# opcouplers.net
KiCad netlist of a schematic drawn in Altium Designer
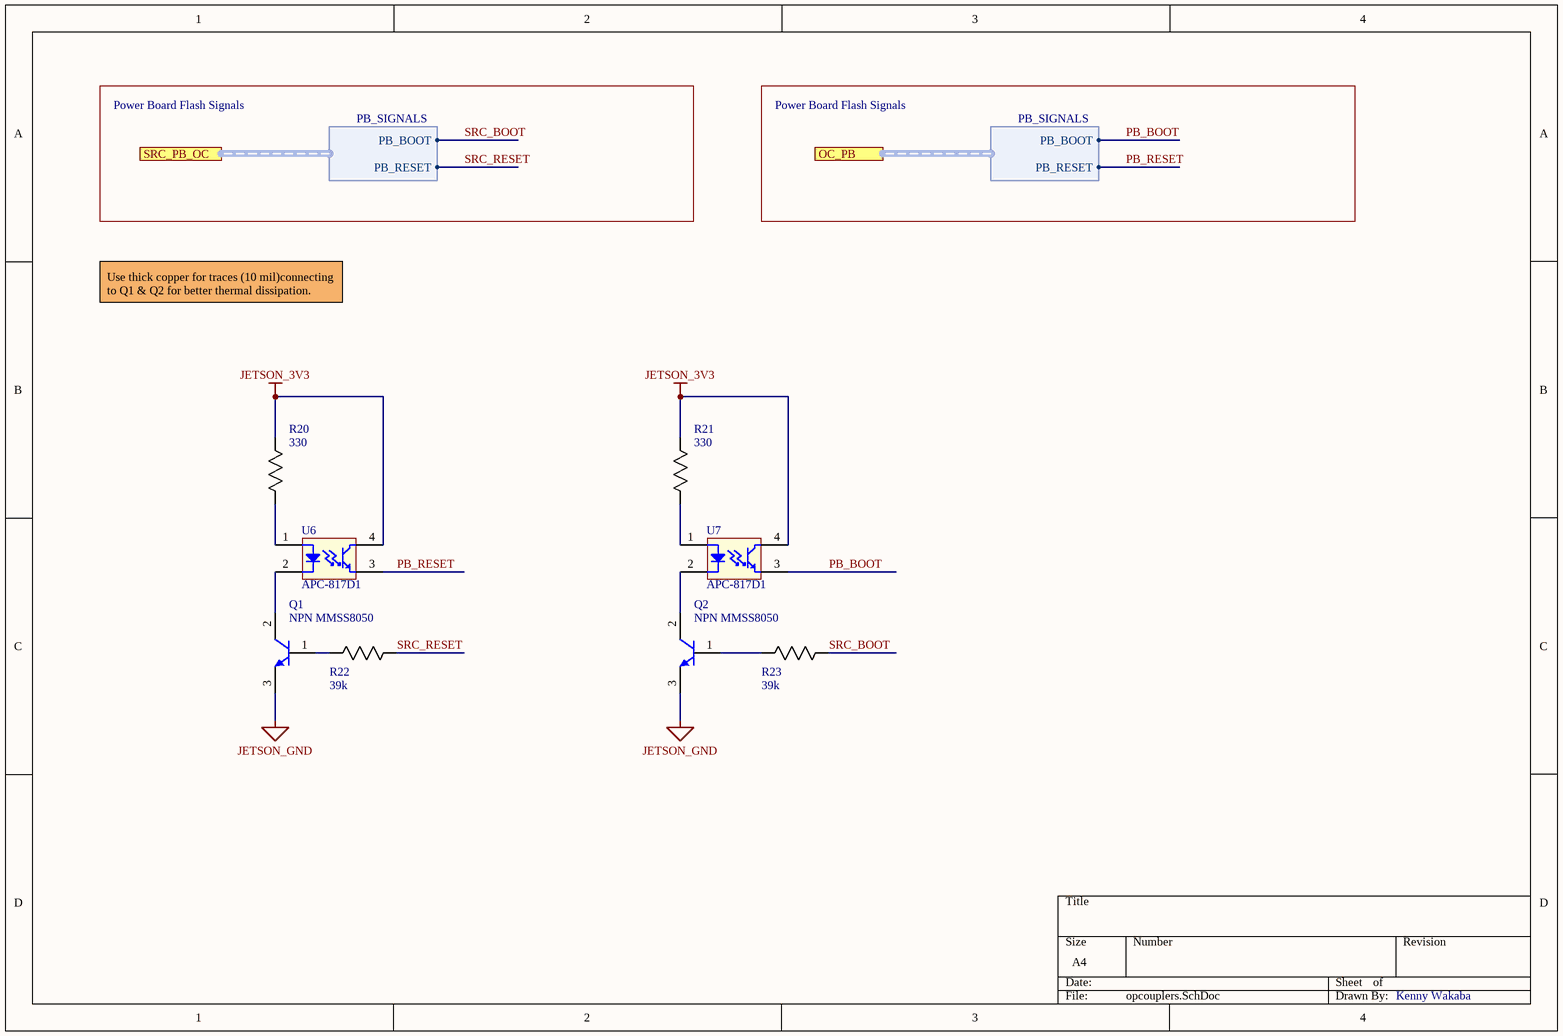
[diagram p0: opcouplers.SchDoc]

(export (version "E")
  (design (tool "Eeschema 10.0.6"))
  (components
    (comp (ref "Q1")
      (value "NPN MMSS8050")
      (footprint "SOT95P237X112-3N")
      (description "Bipolar (BJT) Transistor NPN 25 V 1.5 A 100MHz 625 mW Surface Mount SOT-23")
      (fields (field (name "PART NUMBER") "N_BJT MMSS8050"))
      (libsource (lib "Transistor_Library") (part "NPN MMSS8050"))
    )
    (comp (ref "Q2")
      (value "NPN MMSS8050")
      (footprint "SOT95P237X112-3N")
      (description "Bipolar (BJT) Transistor NPN 25 V 1.5 A 100MHz 625 mW Surface Mount SOT-23")
      (fields (field (name "PART NUMBER") "N_BJT MMSS8050"))
      (libsource (lib "Transistor_Library") (part "NPN MMSS8050"))
    )
    (comp (ref "R20")
      (value "330")
      (footprint "0603")
      (description "Default Resistor Symbol")
      (fields (field (name "TOLERANCE") "5%") (field (name "PART NUMBER") "RES 330.0 1/8W - 5%"))
      (libsource (lib "Resistor_Library") (part "RES_DEFAULT"))
    )
    (comp (ref "R21")
      (value "330")
      (footprint "0603")
      (description "Default Resistor Symbol")
      (fields (field (name "TOLERANCE") "5%") (field (name "PART NUMBER") "RES 330.0 1/8W - 5%"))
      (libsource (lib "Resistor_Library") (part "RES_DEFAULT"))
    )
    (comp (ref "R22")
      (value "39k")
      (footprint "0603")
      (description "Default Resistor Symbol")
      (fields (field (name "TOLERANCE") "1%") (field (name "PART NUMBER") "RES 39k 1/8W"))
      (libsource (lib "Resistor_Library") (part "RES_DEFAULT"))
    )
    (comp (ref "R23")
      (value "39k")
      (footprint "0603")
      (description "Default Resistor Symbol")
      (fields (field (name "TOLERANCE") "1%") (field (name "PART NUMBER") "RES 39k 1/8W"))
      (libsource (lib "Resistor_Library") (part "RES_DEFAULT"))
    )
    (comp (ref "U6")
      (value "APC-817D1")
      (footprint "APC-817D1")
      (description "DIP4, DC Input, Optocoupler")
      (libsource (lib "IC_Library") (part "APC-817D1"))
    )
    (comp (ref "U7")
      (value "APC-817D1")
      (footprint "APC-817D1")
      (description "DIP4, DC Input, Optocoupler")
      (libsource (lib "IC_Library") (part "APC-817D1"))
    )
  )
  (nets
    (net (code "2") (name "/PB_BOOT") (class "Default")
      (node (ref "U7") (pin "3") (pinfunction "3_3") (pintype "passive"))
    )
    (net (code "3") (name "/PB_RESET") (class "Default")
      (node (ref "U6") (pin "3") (pinfunction "3_3") (pintype "passive"))
    )
    (net (code "4") (name "/SRC_BOOT") (class "Default")
      (node (ref "R23") (pin "1") (pinfunction "R1_1") (pintype "passive"))
    )
    (net (code "5") (name "/SRC_RESET") (class "Default")
      (node (ref "R22") (pin "1") (pinfunction "R1_1") (pintype "passive"))
    )
    (net (code "7") (name "JETSON_3V3") (class "Default")
      (node (ref "R20") (pin "2") (pinfunction "R2_2") (pintype "passive"))
      (node (ref "R21") (pin "2") (pinfunction "R2_2") (pintype "passive"))
      (node (ref "U6") (pin "4") (pinfunction "4_4") (pintype "passive"))
      (node (ref "U7") (pin "4") (pinfunction "4_4") (pintype "passive"))
    )
    (net (code "8") (name "JETSON_GND") (class "Default")
      (node (ref "Q1") (pin "3") (pinfunction "E_3") (pintype "passive"))
      (node (ref "Q2") (pin "3") (pinfunction "E_3") (pintype "passive"))
    )
    (net (code "9") (name "Net-(Q1-B)") (class "Default")
      (node (ref "Q1") (pin "1") (pinfunction "B_1") (pintype "passive"))
      (node (ref "R22") (pin "2") (pinfunction "R2_2") (pintype "passive"))
    )
    (net (code "10") (name "Net-(Q1-C)") (class "Default")
      (node (ref "Q1") (pin "2") (pinfunction "C_2") (pintype "passive"))
      (node (ref "U6") (pin "2") (pinfunction "2_2") (pintype "passive"))
    )
    (net (code "11") (name "Net-(Q2-B)") (class "Default")
      (node (ref "Q2") (pin "1") (pinfunction "B_1") (pintype "passive"))
      (node (ref "R23") (pin "2") (pinfunction "R2_2") (pintype "passive"))
    )
    (net (code "12") (name "Net-(Q2-C)") (class "Default")
      (node (ref "Q2") (pin "2") (pinfunction "C_2") (pintype "passive"))
      (node (ref "U7") (pin "2") (pinfunction "2_2") (pintype "passive"))
    )
    (net (code "13") (name "Net-(R20-R1)") (class "Default")
      (node (ref "R20") (pin "1") (pinfunction "R1_1") (pintype "passive"))
      (node (ref "U6") (pin "1") (pinfunction "1_1") (pintype "passive"))
    )
    (net (code "14") (name "Net-(R21-R1)") (class "Default")
      (node (ref "R21") (pin "1") (pinfunction "R1_1") (pintype "passive"))
      (node (ref "U7") (pin "1") (pinfunction "1_1") (pintype "passive"))
    )
  )
)
